# DIGITAL-OUTPUT.net
KiCad netlist of a schematic drawn in Altium Designer
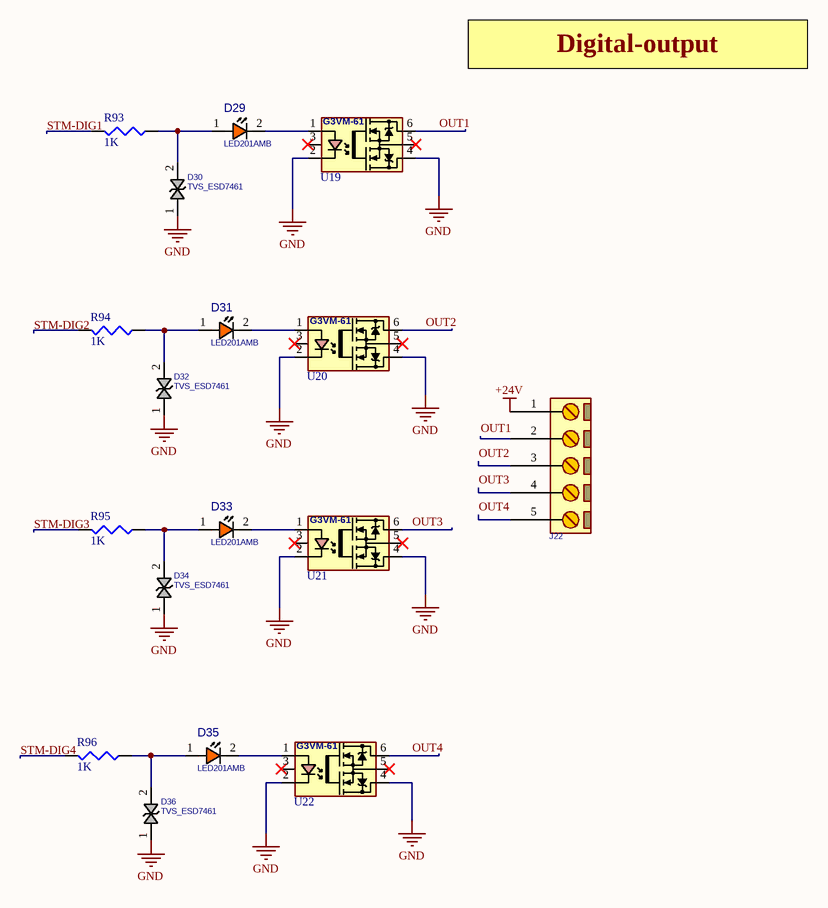
[diagram p0: DIGITAL-OUTPUT.SchDoc]

(export (version "E")
  (design (tool "Eeschema 10.0.6"))
  (components
    (comp (ref "D29")
      (value "LED201AMB")
      (footprint "LED0201AMB")
      (description "LED, SMD, 0201, AMBER")
      (fields (field (name "MANF") "Kingbright") (field (name "MANF_P#") "APG0603SEC-TT"))
      (libsource (lib "led(diode)") (part "LED_SMD_0201_AMB"))
    )
    (comp (ref "D30")
      (value "TVS_ESD7461")
      (footprint "ESD_XDFN2")
      (description "TVS, ESD PROTECT, Bidirectional")
      (fields (field (name "MANF_P#") "ESD7461N2T5G") (field (name "MANF") "ON"))
      (libsource (lib "protect_tvs_esd_fuse") (part "TVS_ESD7461"))
    )
    (comp (ref "D31")
      (value "LED201AMB")
      (footprint "LED0201AMB")
      (description "LED, SMD, 0201, AMBER")
      (fields (field (name "MANF") "Kingbright") (field (name "MANF_P#") "APG0603SEC-TT"))
      (libsource (lib "led(diode)") (part "LED_SMD_0201_AMB"))
    )
    (comp (ref "D32")
      (value "TVS_ESD7461")
      (footprint "ESD_XDFN2")
      (description "TVS, ESD PROTECT, Bidirectional")
      (fields (field (name "MANF_P#") "ESD7461N2T5G") (field (name "MANF") "ON"))
      (libsource (lib "protect_tvs_esd_fuse") (part "TVS_ESD7461"))
    )
    (comp (ref "D33")
      (value "LED201AMB")
      (footprint "LED0201AMB")
      (description "LED, SMD, 0201, AMBER")
      (fields (field (name "MANF") "Kingbright") (field (name "MANF_P#") "APG0603SEC-TT"))
      (libsource (lib "led(diode)") (part "LED_SMD_0201_AMB"))
    )
    (comp (ref "D34")
      (value "TVS_ESD7461")
      (footprint "ESD_XDFN2")
      (description "TVS, ESD PROTECT, Bidirectional")
      (fields (field (name "MANF_P#") "ESD7461N2T5G") (field (name "MANF") "ON"))
      (libsource (lib "protect_tvs_esd_fuse") (part "TVS_ESD7461"))
    )
    (comp (ref "D35")
      (value "LED201AMB")
      (footprint "LED0201AMB")
      (description "LED, SMD, 0201, AMBER")
      (fields (field (name "MANF") "Kingbright") (field (name "MANF_P#") "APG0603SEC-TT"))
      (libsource (lib "led(diode)") (part "LED_SMD_0201_AMB"))
    )
    (comp (ref "D36")
      (value "TVS_ESD7461")
      (footprint "ESD_XDFN2")
      (description "TVS, ESD PROTECT, Bidirectional")
      (fields (field (name "MANF_P#") "ESD7461N2T5G") (field (name "MANF") "ON"))
      (libsource (lib "protect_tvs_esd_fuse") (part "TVS_ESD7461"))
    )
    (comp (ref "J22")
      (value "CONN_TB5")
      (footprint "MSTB_5")
      (description "CONN, PHOENIX MSTB, 5-G, 5.08mm pitch")
      (libsource (lib "conn_power_terminalB") (part "CONN_MSTB_5"))
    )
    (comp (ref "R93")
      (value "1K")
      (footprint "0603L")
      (description "RES SMD 1K OHM 1% 1/10W 0603")
      (fields
        (field (name "DIGI-KEY PART NUMBER") "1276-3484-1-ND")
        (field (name "MANUFACTURER PART NUMBER") "RC1608F102CS")
        (field (name "PUBLISHER") "Altium Limited")
      )
      (libsource (lib "Miscellaneous Devices") (part "Res3"))
    )
    (comp (ref "R94")
      (value "1K")
      (footprint "0603L")
      (description "RES SMD 1K OHM 1% 1/10W 0603")
      (fields
        (field (name "DIGI-KEY PART NUMBER") "1276-3484-1-ND")
        (field (name "MANUFACTURER PART NUMBER") "RC1608F102CS")
        (field (name "PUBLISHER") "Altium Limited")
      )
      (libsource (lib "Miscellaneous Devices") (part "Res3"))
    )
    (comp (ref "R95")
      (value "1K")
      (footprint "0603L")
      (description "RES SMD 1K OHM 1% 1/10W 0603")
      (fields
        (field (name "DIGI-KEY PART NUMBER") "1276-3484-1-ND")
        (field (name "MANUFACTURER PART NUMBER") "RC1608F102CS")
        (field (name "PUBLISHER") "Altium Limited")
      )
      (libsource (lib "Miscellaneous Devices") (part "Res3"))
    )
    (comp (ref "R96")
      (value "1K")
      (footprint "0603L")
      (description "RES SMD 1K OHM 1% 1/10W 0603")
      (fields
        (field (name "DIGI-KEY PART NUMBER") "1276-3484-1-ND")
        (field (name "MANUFACTURER PART NUMBER") "RC1608F102CS")
        (field (name "PUBLISHER") "Altium Limited")
      )
      (libsource (lib "Miscellaneous Devices") (part "Res3"))
    )
    (comp (ref "U19")
      (value "G3VM-61")
      (footprint "DIP_6SMD")
      (description "OPTOCOUPLER, MOS SSR, 6PIN")
      (libsource (lib "optocoupler") (part "OPTC_MOS6P_G3VM-61E1"))
    )
    (comp (ref "U20")
      (value "G3VM-61")
      (footprint "DIP_6SMD")
      (description "OPTOCOUPLER, MOS SSR, 6PIN")
      (libsource (lib "optocoupler") (part "OPTC_MOS6P_G3VM-61E1"))
    )
    (comp (ref "U21")
      (value "G3VM-61")
      (footprint "DIP_6SMD")
      (description "OPTOCOUPLER, MOS SSR, 6PIN")
      (libsource (lib "optocoupler") (part "OPTC_MOS6P_G3VM-61E1"))
    )
    (comp (ref "U22")
      (value "G3VM-61")
      (footprint "DIP_6SMD")
      (description "OPTOCOUPLER, MOS SSR, 6PIN")
      (libsource (lib "optocoupler") (part "OPTC_MOS6P_G3VM-61E1"))
    )
  )
  (nets
    (net (code "1") (name "+24V") (class "Default")
      (node (ref "J22") (pin "1") (pinfunction "1_1") (pintype "passive"))
    )
    (net (code "2") (name "/OUT1") (class "Default")
      (node (ref "J22") (pin "2") (pinfunction "2_2") (pintype "passive"))
      (node (ref "U19") (pin "6") (pinfunction "6_6") (pintype "passive"))
    )
    (net (code "3") (name "/OUT2") (class "Default")
      (node (ref "J22") (pin "3") (pinfunction "3_3") (pintype "passive"))
      (node (ref "U20") (pin "6") (pinfunction "6_6") (pintype "passive"))
    )
    (net (code "4") (name "/OUT3") (class "Default")
      (node (ref "J22") (pin "4") (pinfunction "4_4") (pintype "passive"))
      (node (ref "U21") (pin "6") (pinfunction "6_6") (pintype "passive"))
    )
    (net (code "5") (name "/OUT4") (class "Default")
      (node (ref "J22") (pin "5") (pinfunction "5_5") (pintype "passive"))
      (node (ref "U22") (pin "6") (pinfunction "6_6") (pintype "passive"))
    )
    (net (code "6") (name "/STM-DIG1") (class "Default")
      (node (ref "R93") (pin "2") (pinfunction "2_2") (pintype "passive"))
    )
    (net (code "7") (name "/STM-DIG2") (class "Default")
      (node (ref "R94") (pin "2") (pinfunction "2_2") (pintype "passive"))
    )
    (net (code "8") (name "/STM-DIG3") (class "Default")
      (node (ref "R95") (pin "2") (pinfunction "2_2") (pintype "passive"))
    )
    (net (code "9") (name "/STM-DIG4") (class "Default")
      (node (ref "R96") (pin "2") (pinfunction "2_2") (pintype "passive"))
    )
    (net (code "10") (name "GND") (class "Default")
      (node (ref "D30") (pin "1") (pinfunction "1_1") (pintype "passive"))
      (node (ref "D32") (pin "1") (pinfunction "1_1") (pintype "passive"))
      (node (ref "D34") (pin "1") (pinfunction "1_1") (pintype "passive"))
      (node (ref "D36") (pin "1") (pinfunction "1_1") (pintype "passive"))
      (node (ref "U19") (pin "2") (pinfunction "K_2") (pintype "passive"))
      (node (ref "U19") (pin "4") (pinfunction "4_4") (pintype "passive"))
      (node (ref "U20") (pin "2") (pinfunction "K_2") (pintype "passive"))
      (node (ref "U20") (pin "4") (pinfunction "4_4") (pintype "passive"))
      (node (ref "U21") (pin "2") (pinfunction "K_2") (pintype "passive"))
      (node (ref "U21") (pin "4") (pinfunction "4_4") (pintype "passive"))
      (node (ref "U22") (pin "2") (pinfunction "K_2") (pintype "passive"))
      (node (ref "U22") (pin "4") (pinfunction "4_4") (pintype "passive"))
    )
    (net (code "11") (name "Net-(D29-ANODE)") (class "Default")
      (node (ref "D29") (pin "1") (pinfunction "ANODE_1") (pintype "passive"))
      (node (ref "D30") (pin "2") (pinfunction "2_2") (pintype "passive"))
      (node (ref "R93") (pin "1") (pinfunction "1_1") (pintype "passive"))
    )
    (net (code "12") (name "Net-(D29-CATHODE)") (class "Default")
      (node (ref "D29") (pin "2") (pinfunction "CATHODE_2") (pintype "passive"))
      (node (ref "U19") (pin "1") (pinfunction "A_1") (pintype "passive"))
    )
    (net (code "13") (name "Net-(D31-ANODE)") (class "Default")
      (node (ref "D31") (pin "1") (pinfunction "ANODE_1") (pintype "passive"))
      (node (ref "D32") (pin "2") (pinfunction "2_2") (pintype "passive"))
      (node (ref "R94") (pin "1") (pinfunction "1_1") (pintype "passive"))
    )
    (net (code "14") (name "Net-(D31-CATHODE)") (class "Default")
      (node (ref "D31") (pin "2") (pinfunction "CATHODE_2") (pintype "passive"))
      (node (ref "U20") (pin "1") (pinfunction "A_1") (pintype "passive"))
    )
    (net (code "15") (name "Net-(D33-ANODE)") (class "Default")
      (node (ref "D33") (pin "1") (pinfunction "ANODE_1") (pintype "passive"))
      (node (ref "D34") (pin "2") (pinfunction "2_2") (pintype "passive"))
      (node (ref "R95") (pin "1") (pinfunction "1_1") (pintype "passive"))
    )
    (net (code "16") (name "Net-(D33-CATHODE)") (class "Default")
      (node (ref "D33") (pin "2") (pinfunction "CATHODE_2") (pintype "passive"))
      (node (ref "U21") (pin "1") (pinfunction "A_1") (pintype "passive"))
    )
    (net (code "17") (name "Net-(D35-ANODE)") (class "Default")
      (node (ref "D35") (pin "1") (pinfunction "ANODE_1") (pintype "passive"))
      (node (ref "D36") (pin "2") (pinfunction "2_2") (pintype "passive"))
      (node (ref "R96") (pin "1") (pinfunction "1_1") (pintype "passive"))
    )
    (net (code "18") (name "Net-(D35-CATHODE)") (class "Default")
      (node (ref "D35") (pin "2") (pinfunction "CATHODE_2") (pintype "passive"))
      (node (ref "U22") (pin "1") (pinfunction "A_1") (pintype "passive"))
    )
    (net (code "19") (name "unconnected-(U19-Pad3)") (class "Default")
      (node (ref "U19") (pin "3") (pinfunction "3_3") (pintype "passive+no_connect"))
    )
    (net (code "20") (name "unconnected-(U19-Pad5)") (class "Default")
      (node (ref "U19") (pin "5") (pinfunction "5_5") (pintype "passive+no_connect"))
    )
    (net (code "21") (name "unconnected-(U20-Pad3)") (class "Default")
      (node (ref "U20") (pin "3") (pinfunction "3_3") (pintype "passive+no_connect"))
    )
    (net (code "22") (name "unconnected-(U20-Pad5)") (class "Default")
      (node (ref "U20") (pin "5") (pinfunction "5_5") (pintype "passive+no_connect"))
    )
    (net (code "23") (name "unconnected-(U21-Pad3)") (class "Default")
      (node (ref "U21") (pin "3") (pinfunction "3_3") (pintype "passive+no_connect"))
    )
    (net (code "24") (name "unconnected-(U21-Pad5)") (class "Default")
      (node (ref "U21") (pin "5") (pinfunction "5_5") (pintype "passive+no_connect"))
    )
    (net (code "25") (name "unconnected-(U22-Pad3)") (class "Default")
      (node (ref "U22") (pin "3") (pinfunction "3_3") (pintype "passive+no_connect"))
    )
    (net (code "26") (name "unconnected-(U22-Pad5)") (class "Default")
      (node (ref "U22") (pin "5") (pinfunction "5_5") (pintype "passive+no_connect"))
    )
  )
)
